# due.net
KiCad netlist of a schematic drawn in EAGLE
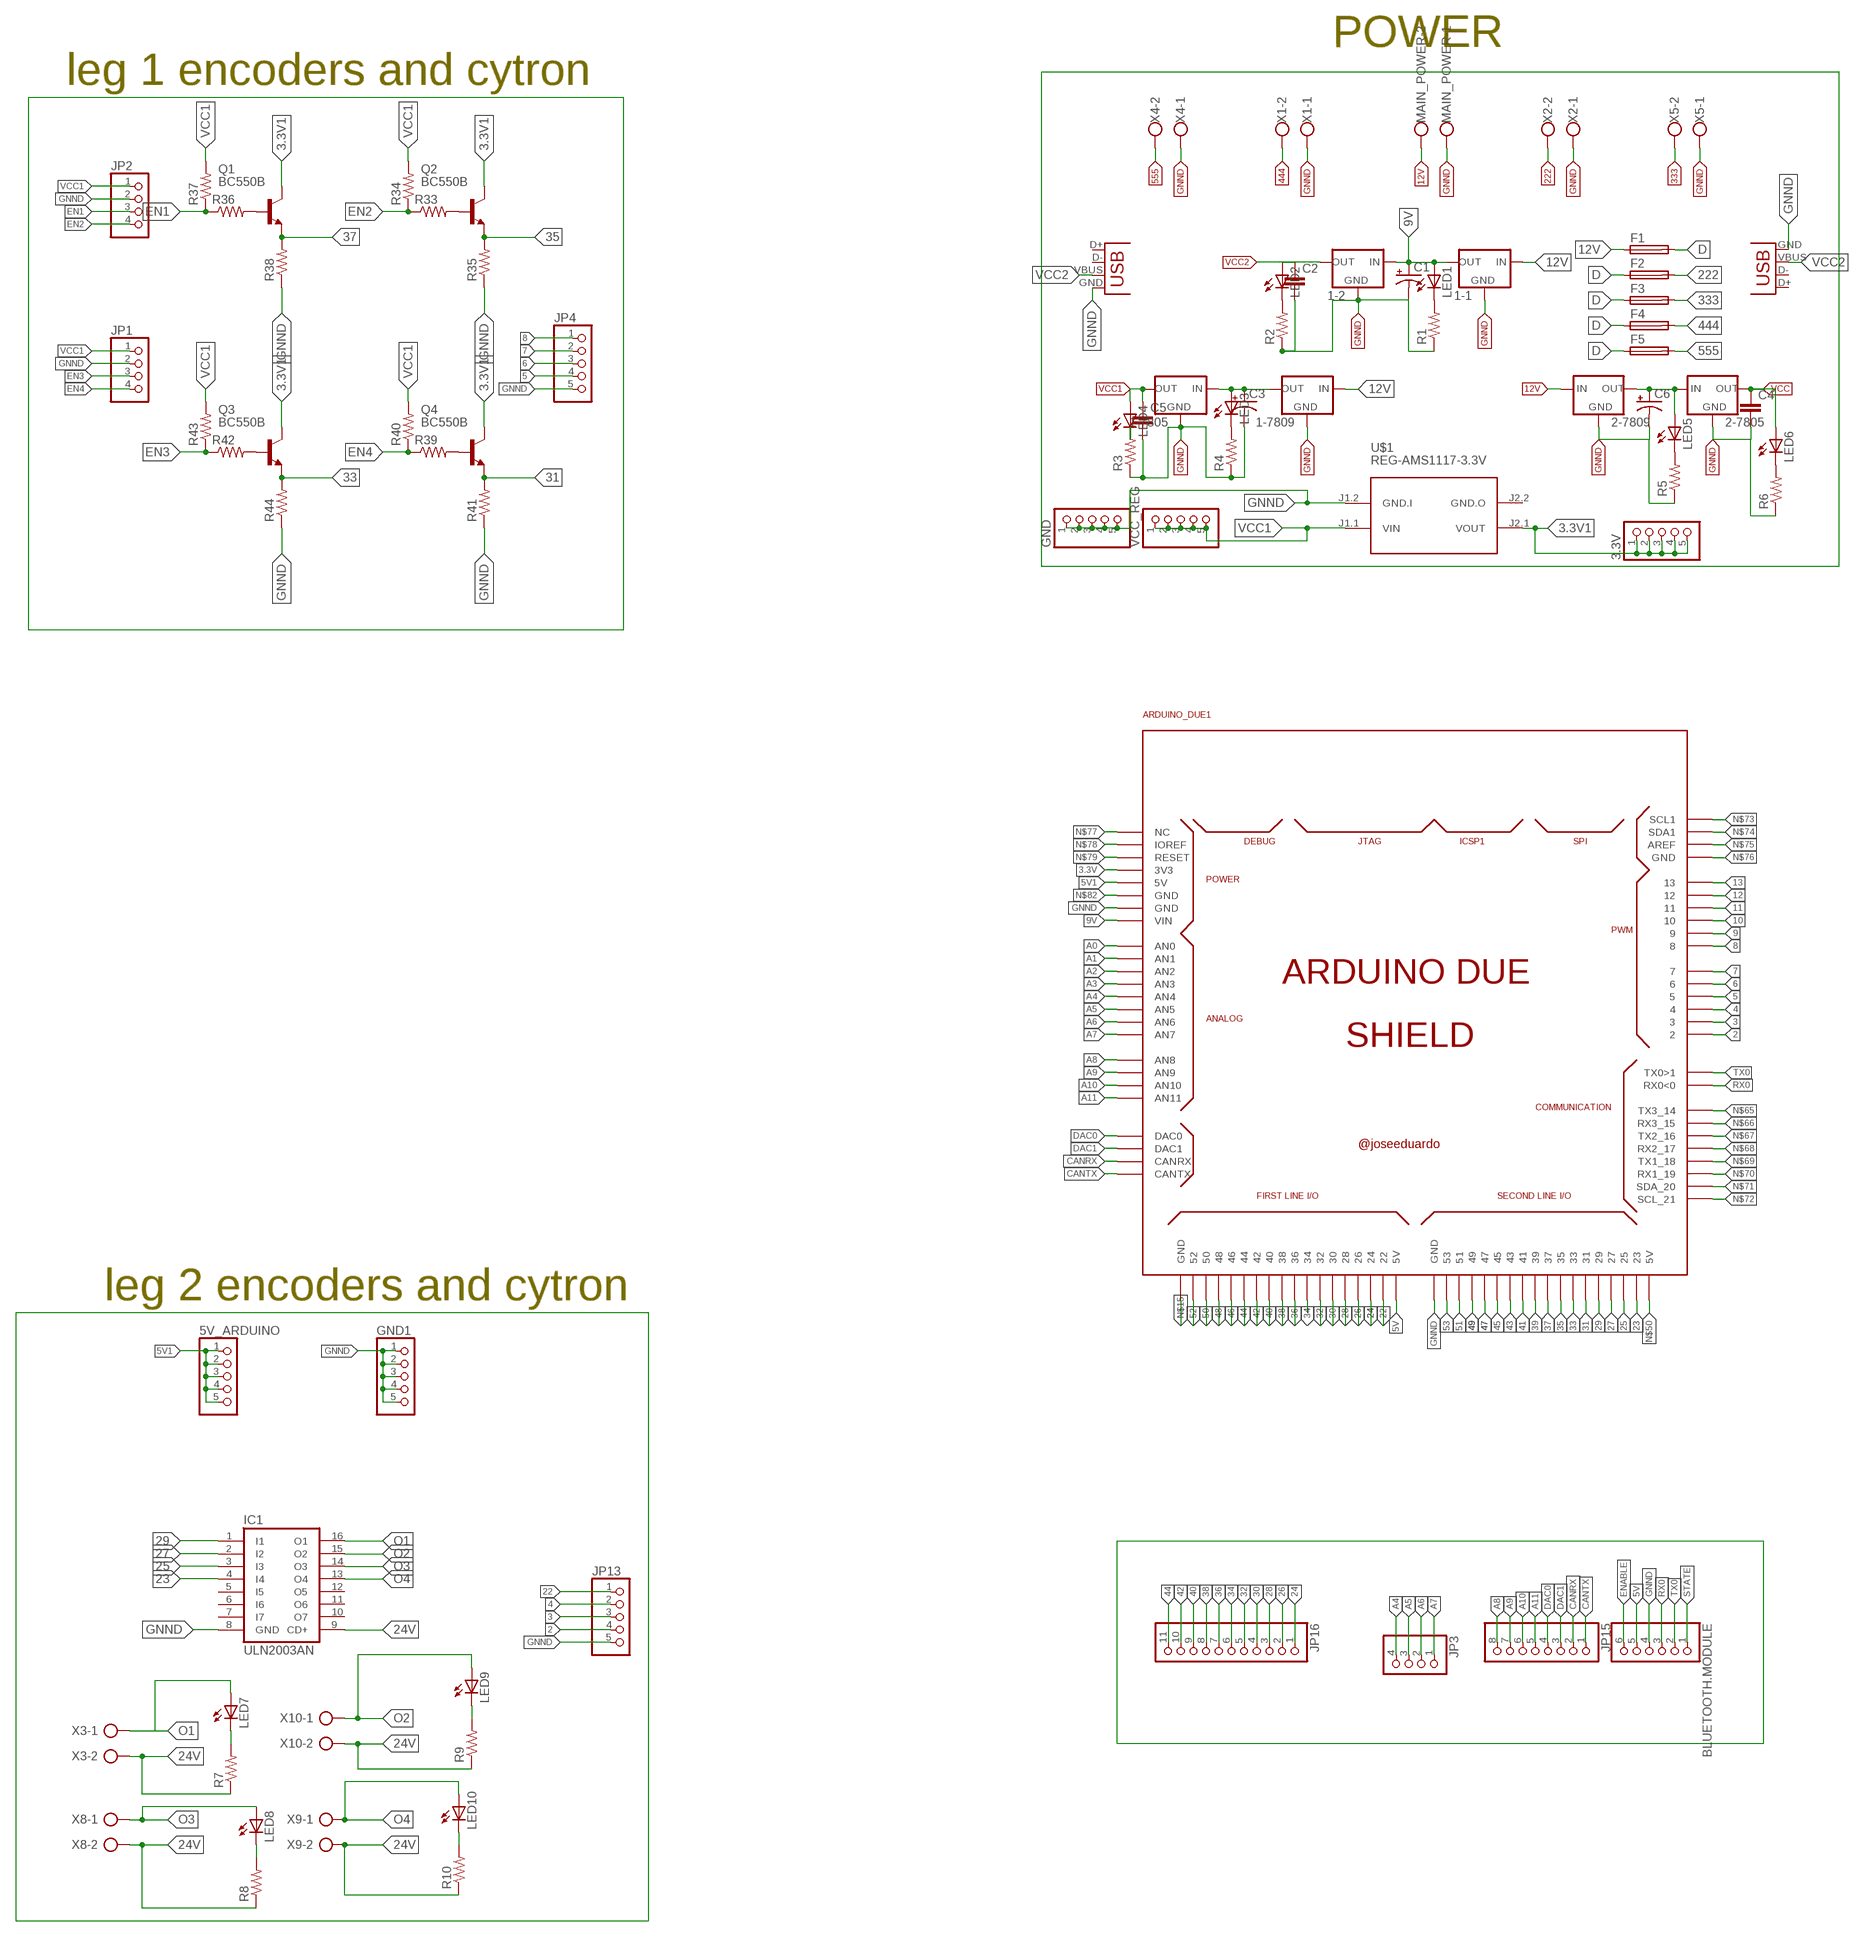
[diagram p0: schematic, sheet 1, part 1 of 2]
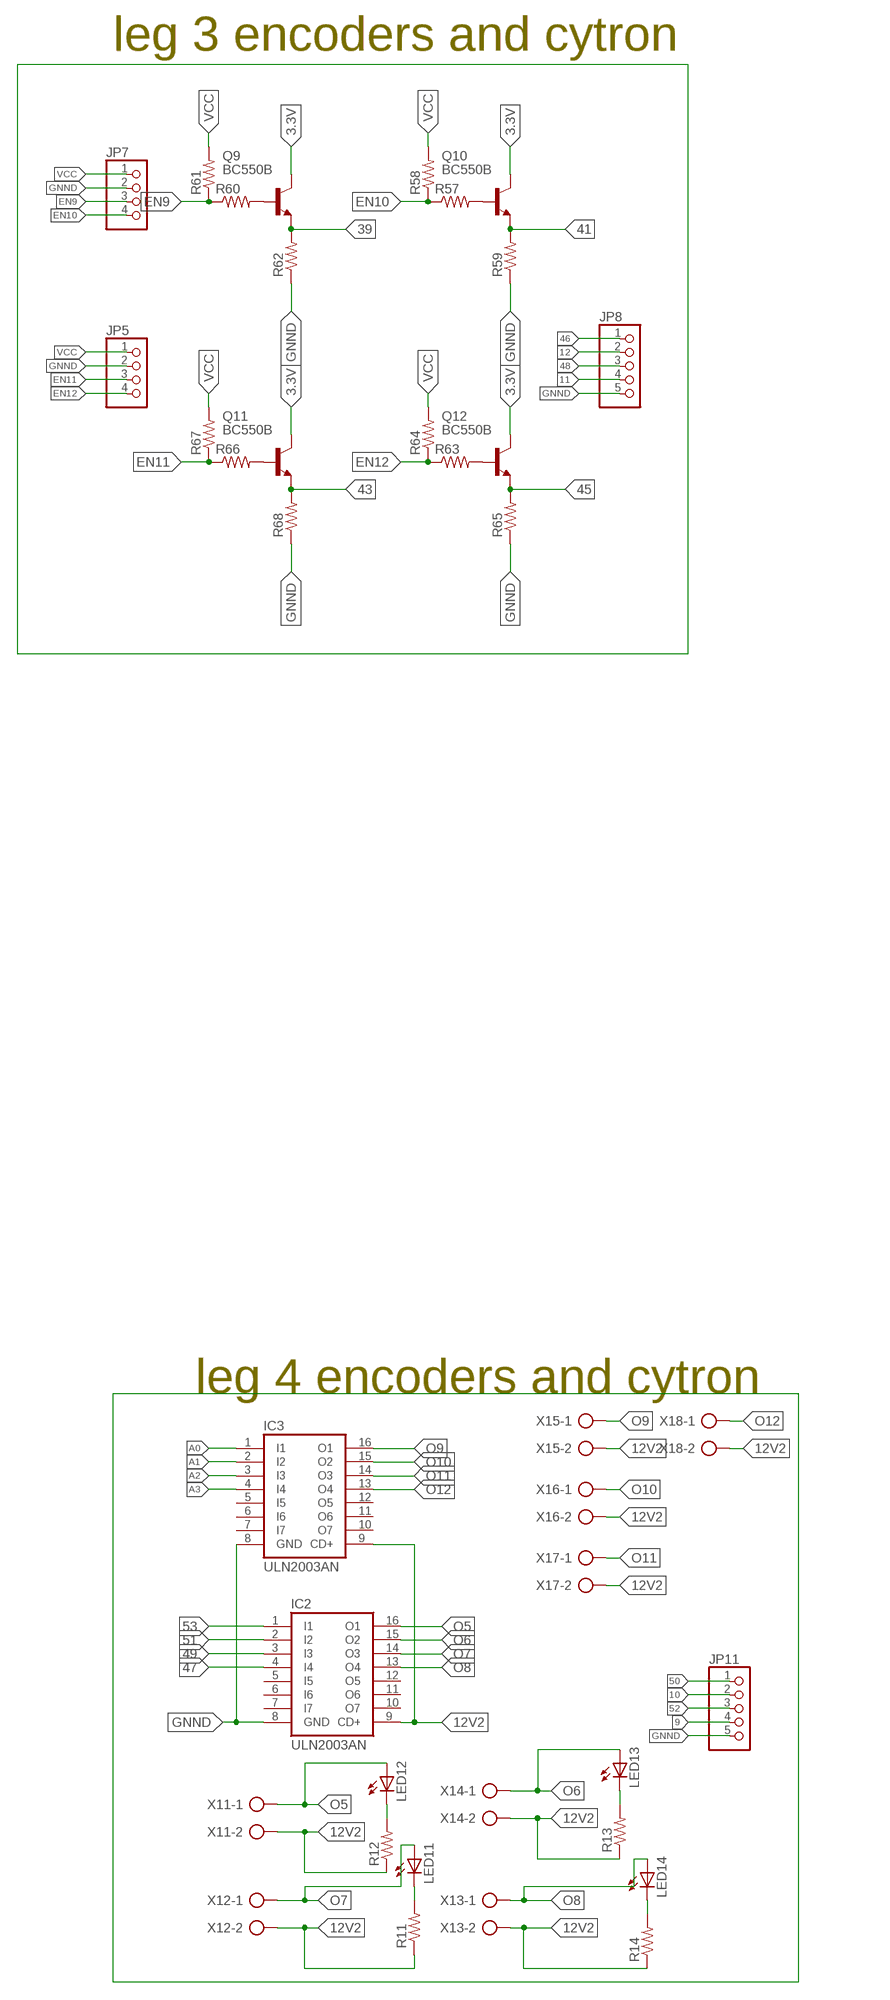
[diagram p1: schematic, sheet 1, part 2 of 2]

(export (version "E")
  (design (tool "Eeschema 10.0.6"))
  (components
    (comp (ref "1-1")
      (value "78XXS")
      (footprint "eagle-import:78XXS")
      (libsource (lib "eagle-import") (part "78XXS"))
    )
    (comp (ref "1-2")
      (value "78XXS")
      (footprint "eagle-import:78XXS")
      (libsource (lib "eagle-import") (part "78XXS"))
    )
    (comp (ref "1-7805")
      (value "78XXS")
      (footprint "eagle-import:78XXS")
      (libsource (lib "eagle-import") (part "78XXS"))
    )
    (comp (ref "1-7809")
      (value "78XXS")
      (footprint "eagle-import:78XXS")
      (libsource (lib "eagle-import") (part "78XXS"))
    )
    (comp (ref "2-7805")
      (value "78XXS")
      (footprint "eagle-import:78XXS")
      (libsource (lib "eagle-import") (part "78XXS"))
    )
    (comp (ref "2-7809")
      (value "78XXS")
      (footprint "eagle-import:78XXS")
      (libsource (lib "eagle-import") (part "78XXS"))
    )
    (comp (ref "3.3V")
      (value "PINHD-1X5")
      (footprint "eagle-import:1X05")
      (libsource (lib "eagle-import") (part "PINHD-1X5"))
    )
    (comp (ref "5V_ARDUINO")
      (value "PINHD-1X5")
      (footprint "eagle-import:1X05")
      (libsource (lib "eagle-import") (part "PINHD-1X5"))
    )
    (comp (ref "ARDUINO_DUE1")
      (value "ARDUINO_DUE_SHIELD")
      (footprint "eagle-import:ARDUINO_DUE_SHIELD")
      (libsource (lib "eagle-import") (part "ARDUINO_DUE_SHIELD"))
    )
    (comp (ref "BLUETOOTH.MODULE")
      (value "PINHD-1X6")
      (footprint "eagle-import:1X06")
      (libsource (lib "eagle-import") (part "PINHD-1X6"))
    )
    (comp (ref "C1")
      (value "CPOL-USE2.5-7")
      (footprint "eagle-import:E2,5-7")
      (libsource (lib "eagle-import") (part "CPOL-USE2.5-7"))
    )
    (comp (ref "C2")
      (value "C-EU025-025X050")
      (footprint "eagle-import:C025-025X050")
      (libsource (lib "eagle-import") (part "C-EU025-025X050"))
    )
    (comp (ref "C3")
      (value "CPOL-USE2.5-7")
      (footprint "eagle-import:E2,5-7")
      (libsource (lib "eagle-import") (part "CPOL-USE2.5-7"))
    )
    (comp (ref "C4")
      (value "C-EU025-025X050")
      (footprint "eagle-import:C025-025X050")
      (libsource (lib "eagle-import") (part "C-EU025-025X050"))
    )
    (comp (ref "C5")
      (value "C-EU025-025X050")
      (footprint "eagle-import:C025-025X050")
      (libsource (lib "eagle-import") (part "C-EU025-025X050"))
    )
    (comp (ref "C6")
      (value "CPOL-USE2.5-7")
      (footprint "eagle-import:E2,5-7")
      (libsource (lib "eagle-import") (part "CPOL-USE2.5-7"))
    )
    (comp (ref "F1")
      (value "SH22,5A")
      (footprint "eagle-import:SH22,5A")
      (fields (field (name "MPN") "0031.7701.11"))
      (libsource (lib "eagle-import") (part "SH22,5A"))
    )
    (comp (ref "F2")
      (value "SH22,5A")
      (footprint "eagle-import:SH22,5A")
      (fields (field (name "MPN") "0031.7701.11"))
      (libsource (lib "eagle-import") (part "SH22,5A"))
    )
    (comp (ref "F3")
      (value "SH22,5A")
      (footprint "eagle-import:SH22,5A")
      (fields (field (name "MPN") "0031.7701.11"))
      (libsource (lib "eagle-import") (part "SH22,5A"))
    )
    (comp (ref "F4")
      (value "SH22,5A")
      (footprint "eagle-import:SH22,5A")
      (fields (field (name "MPN") "0031.7701.11"))
      (libsource (lib "eagle-import") (part "SH22,5A"))
    )
    (comp (ref "F5")
      (value "SH22,5A")
      (footprint "eagle-import:SH22,5A")
      (fields (field (name "MPN") "0031.7701.11"))
      (libsource (lib "eagle-import") (part "SH22,5A"))
    )
    (comp (ref "GND")
      (value "PINHD-1X5")
      (footprint "eagle-import:1X05")
      (libsource (lib "eagle-import") (part "PINHD-1X5"))
    )
    (comp (ref "GND1")
      (value "PINHD-1X5")
      (footprint "eagle-import:1X05")
      (libsource (lib "eagle-import") (part "PINHD-1X5"))
    )
    (comp (ref "IC1")
      (value "ULN2003AN")
      (footprint "eagle-import:DIL16")
      (libsource (lib "eagle-import") (part "ULN2003AN"))
    )
    (comp (ref "IC2")
      (value "ULN2003AN")
      (footprint "eagle-import:DIL16")
      (libsource (lib "eagle-import") (part "ULN2003AN"))
    )
    (comp (ref "IC3")
      (value "ULN2003AN")
      (footprint "eagle-import:DIL16")
      (libsource (lib "eagle-import") (part "ULN2003AN"))
    )
    (comp (ref "JP1")
      (value "PINHD-1X4")
      (footprint "eagle-import:1X04")
      (libsource (lib "eagle-import") (part "PINHD-1X4"))
    )
    (comp (ref "JP2")
      (value "PINHD-1X4")
      (footprint "eagle-import:1X04")
      (libsource (lib "eagle-import") (part "PINHD-1X4"))
    )
    (comp (ref "JP3")
      (value "PINHD-1X4")
      (footprint "eagle-import:1X04")
      (libsource (lib "eagle-import") (part "PINHD-1X4"))
    )
    (comp (ref "JP4")
      (value "PINHD-1X5")
      (footprint "eagle-import:1X05")
      (libsource (lib "eagle-import") (part "PINHD-1X5"))
    )
    (comp (ref "JP5")
      (value "PINHD-1X4")
      (footprint "eagle-import:1X04")
      (libsource (lib "eagle-import") (part "PINHD-1X4"))
    )
    (comp (ref "JP7")
      (value "PINHD-1X4")
      (footprint "eagle-import:1X04")
      (libsource (lib "eagle-import") (part "PINHD-1X4"))
    )
    (comp (ref "JP8")
      (value "PINHD-1X5")
      (footprint "eagle-import:1X05")
      (libsource (lib "eagle-import") (part "PINHD-1X5"))
    )
    (comp (ref "JP11")
      (value "PINHD-1X5")
      (footprint "eagle-import:1X05")
      (libsource (lib "eagle-import") (part "PINHD-1X5"))
    )
    (comp (ref "JP13")
      (value "PINHD-1X5")
      (footprint "eagle-import:1X05")
      (libsource (lib "eagle-import") (part "PINHD-1X5"))
    )
    (comp (ref "JP15")
      (value "PINHD-1X8")
      (footprint "eagle-import:1X08")
      (libsource (lib "eagle-import") (part "PINHD-1X8"))
    )
    (comp (ref "JP16")
      (value "PINHD-1X11")
      (footprint "eagle-import:1X11")
      (libsource (lib "eagle-import") (part "PINHD-1X11"))
    )
    (comp (ref "LED1")
      (value "LED3MM")
      (footprint "eagle-import:LED3MM")
      (libsource (lib "eagle-import") (part "LED3MM"))
    )
    (comp (ref "LED2")
      (value "LED3MM")
      (footprint "eagle-import:LED3MM")
      (libsource (lib "eagle-import") (part "LED3MM"))
    )
    (comp (ref "LED3")
      (value "LED3MM")
      (footprint "eagle-import:LED3MM")
      (libsource (lib "eagle-import") (part "LED3MM"))
    )
    (comp (ref "LED4")
      (value "LED3MM")
      (footprint "eagle-import:LED3MM")
      (libsource (lib "eagle-import") (part "LED3MM"))
    )
    (comp (ref "LED5")
      (value "LED3MM")
      (footprint "eagle-import:LED3MM")
      (libsource (lib "eagle-import") (part "LED3MM"))
    )
    (comp (ref "LED6")
      (value "LED3MM")
      (footprint "eagle-import:LED3MM")
      (libsource (lib "eagle-import") (part "LED3MM"))
    )
    (comp (ref "LED7")
      (value "LED3MM")
      (footprint "eagle-import:LED3MM")
      (libsource (lib "eagle-import") (part "LED3MM"))
    )
    (comp (ref "LED8")
      (value "LED3MM")
      (footprint "eagle-import:LED3MM")
      (libsource (lib "eagle-import") (part "LED3MM"))
    )
    (comp (ref "LED9")
      (value "LED3MM")
      (footprint "eagle-import:LED3MM")
      (libsource (lib "eagle-import") (part "LED3MM"))
    )
    (comp (ref "LED10")
      (value "LED3MM")
      (footprint "eagle-import:LED3MM")
      (libsource (lib "eagle-import") (part "LED3MM"))
    )
    (comp (ref "LED11")
      (value "LED3MM")
      (footprint "eagle-import:LED3MM")
      (libsource (lib "eagle-import") (part "LED3MM"))
    )
    (comp (ref "LED12")
      (value "LED3MM")
      (footprint "eagle-import:LED3MM")
      (libsource (lib "eagle-import") (part "LED3MM"))
    )
    (comp (ref "LED13")
      (value "LED3MM")
      (footprint "eagle-import:LED3MM")
      (libsource (lib "eagle-import") (part "LED3MM"))
    )
    (comp (ref "LED14")
      (value "LED3MM")
      (footprint "eagle-import:LED3MM")
      (libsource (lib "eagle-import") (part "LED3MM"))
    )
    (comp (ref "MAIN_POWER")
      (value "W237-113")
      (footprint "eagle-import:W237-113")
      (libsource (lib "eagle-import") (part "W237-113"))
    )
    (comp (ref "Q1")
      (value "BC550B")
      (footprint "eagle-import:TO92-EBC")
      (libsource (lib "eagle-import") (part "BC550B"))
    )
    (comp (ref "Q2")
      (value "BC550B")
      (footprint "eagle-import:TO92-EBC")
      (libsource (lib "eagle-import") (part "BC550B"))
    )
    (comp (ref "Q3")
      (value "BC550B")
      (footprint "eagle-import:TO92-EBC")
      (libsource (lib "eagle-import") (part "BC550B"))
    )
    (comp (ref "Q4")
      (value "BC550B")
      (footprint "eagle-import:TO92-EBC")
      (libsource (lib "eagle-import") (part "BC550B"))
    )
    (comp (ref "Q9")
      (value "BC550B")
      (footprint "eagle-import:TO92-EBC")
      (libsource (lib "eagle-import") (part "BC550B"))
    )
    (comp (ref "Q10")
      (value "BC550B")
      (footprint "eagle-import:TO92-EBC")
      (libsource (lib "eagle-import") (part "BC550B"))
    )
    (comp (ref "Q11")
      (value "BC550B")
      (footprint "eagle-import:TO92-EBC")
      (libsource (lib "eagle-import") (part "BC550B"))
    )
    (comp (ref "Q12")
      (value "BC550B")
      (footprint "eagle-import:TO92-EBC")
      (libsource (lib "eagle-import") (part "BC550B"))
    )
    (comp (ref "R1")
      (value "R-US_0204/7")
      (footprint "eagle-import:0204_7")
      (libsource (lib "eagle-import") (part "R-US_0204/7"))
    )
    (comp (ref "R2")
      (value "R-US_0204/5")
      (footprint "eagle-import:0204_5")
      (libsource (lib "eagle-import") (part "R-US_0204/5"))
    )
    (comp (ref "R3")
      (value "R-US_0204/5")
      (footprint "eagle-import:0204_5")
      (libsource (lib "eagle-import") (part "R-US_0204/5"))
    )
    (comp (ref "R4")
      (value "R-US_0204/5")
      (footprint "eagle-import:0204_5")
      (libsource (lib "eagle-import") (part "R-US_0204/5"))
    )
    (comp (ref "R5")
      (value "R-US_0204/7")
      (footprint "eagle-import:0204_7")
      (libsource (lib "eagle-import") (part "R-US_0204/7"))
    )
    (comp (ref "R6")
      (value "R-US_0204/5")
      (footprint "eagle-import:0204_5")
      (libsource (lib "eagle-import") (part "R-US_0204/5"))
    )
    (comp (ref "R7")
      (value "R-US_0204/5")
      (footprint "eagle-import:0204_5")
      (libsource (lib "eagle-import") (part "R-US_0204/5"))
    )
    (comp (ref "R8")
      (value "R-US_0204/5")
      (footprint "eagle-import:0204_5")
      (libsource (lib "eagle-import") (part "R-US_0204/5"))
    )
    (comp (ref "R9")
      (value "R-US_0204/5")
      (footprint "eagle-import:0204_5")
      (libsource (lib "eagle-import") (part "R-US_0204/5"))
    )
    (comp (ref "R10")
      (value "R-US_0204/5")
      (footprint "eagle-import:0204_5")
      (libsource (lib "eagle-import") (part "R-US_0204/5"))
    )
    (comp (ref "R11")
      (value "R-US_0204/5")
      (footprint "eagle-import:0204_5")
      (libsource (lib "eagle-import") (part "R-US_0204/5"))
    )
    (comp (ref "R12")
      (value "R-US_0204/5")
      (footprint "eagle-import:0204_5")
      (libsource (lib "eagle-import") (part "R-US_0204/5"))
    )
    (comp (ref "R13")
      (value "R-US_0204/5")
      (footprint "eagle-import:0204_5")
      (libsource (lib "eagle-import") (part "R-US_0204/5"))
    )
    (comp (ref "R14")
      (value "R-US_0204/5")
      (footprint "eagle-import:0204_5")
      (libsource (lib "eagle-import") (part "R-US_0204/5"))
    )
    (comp (ref "R33")
      (value "R-US_0207/12")
      (footprint "eagle-import:0207_12")
      (libsource (lib "eagle-import") (part "R-US_0207/12"))
    )
    (comp (ref "R34")
      (value "R-US_0204/5")
      (footprint "eagle-import:0204_5")
      (libsource (lib "eagle-import") (part "R-US_0204/5"))
    )
    (comp (ref "R35")
      (value "R-US_0207/12")
      (footprint "eagle-import:0207_12")
      (libsource (lib "eagle-import") (part "R-US_0207/12"))
    )
    (comp (ref "R36")
      (value "R-US_0204/7")
      (footprint "eagle-import:0204_7")
      (libsource (lib "eagle-import") (part "R-US_0204/7"))
    )
    (comp (ref "R37")
      (value "R-US_0204/5")
      (footprint "eagle-import:0204_5")
      (libsource (lib "eagle-import") (part "R-US_0204/5"))
    )
    (comp (ref "R38")
      (value "R-US_0204/7")
      (footprint "eagle-import:0204_7")
      (libsource (lib "eagle-import") (part "R-US_0204/7"))
    )
    (comp (ref "R39")
      (value "R-US_0207/12")
      (footprint "eagle-import:0207_12")
      (libsource (lib "eagle-import") (part "R-US_0207/12"))
    )
    (comp (ref "R40")
      (value "R-US_0204/5")
      (footprint "eagle-import:0204_5")
      (libsource (lib "eagle-import") (part "R-US_0204/5"))
    )
    (comp (ref "R41")
      (value "R-US_0207/12")
      (footprint "eagle-import:0207_12")
      (libsource (lib "eagle-import") (part "R-US_0207/12"))
    )
    (comp (ref "R42")
      (value "R-US_0204/7")
      (footprint "eagle-import:0204_7")
      (libsource (lib "eagle-import") (part "R-US_0204/7"))
    )
    (comp (ref "R43")
      (value "R-US_0204/5")
      (footprint "eagle-import:0204_5")
      (libsource (lib "eagle-import") (part "R-US_0204/5"))
    )
    (comp (ref "R44")
      (value "R-US_0204/7")
      (footprint "eagle-import:0204_7")
      (libsource (lib "eagle-import") (part "R-US_0204/7"))
    )
    (comp (ref "R57")
      (value "R-US_0207/12")
      (footprint "eagle-import:0207_12")
      (libsource (lib "eagle-import") (part "R-US_0207/12"))
    )
    (comp (ref "R58")
      (value "R-US_0204/5")
      (footprint "eagle-import:0204_5")
      (libsource (lib "eagle-import") (part "R-US_0204/5"))
    )
    (comp (ref "R59")
      (value "R-US_0207/12")
      (footprint "eagle-import:0207_12")
      (libsource (lib "eagle-import") (part "R-US_0207/12"))
    )
    (comp (ref "R60")
      (value "R-US_0204/7")
      (footprint "eagle-import:0204_7")
      (libsource (lib "eagle-import") (part "R-US_0204/7"))
    )
    (comp (ref "R61")
      (value "R-US_0204/5")
      (footprint "eagle-import:0204_5")
      (libsource (lib "eagle-import") (part "R-US_0204/5"))
    )
    (comp (ref "R62")
      (value "R-US_0204/7")
      (footprint "eagle-import:0204_7")
      (libsource (lib "eagle-import") (part "R-US_0204/7"))
    )
    (comp (ref "R63")
      (value "R-US_0207/12")
      (footprint "eagle-import:0207_12")
      (libsource (lib "eagle-import") (part "R-US_0207/12"))
    )
    (comp (ref "R64")
      (value "R-US_0204/5")
      (footprint "eagle-import:0204_5")
      (libsource (lib "eagle-import") (part "R-US_0204/5"))
    )
    (comp (ref "R65")
      (value "R-US_0207/12")
      (footprint "eagle-import:0207_12")
      (libsource (lib "eagle-import") (part "R-US_0207/12"))
    )
    (comp (ref "R66")
      (value "R-US_0204/7")
      (footprint "eagle-import:0204_7")
      (libsource (lib "eagle-import") (part "R-US_0204/7"))
    )
    (comp (ref "R67")
      (value "R-US_0204/5")
      (footprint "eagle-import:0204_5")
      (libsource (lib "eagle-import") (part "R-US_0204/5"))
    )
    (comp (ref "R68")
      (value "R-US_0204/7")
      (footprint "eagle-import:0204_7")
      (libsource (lib "eagle-import") (part "R-US_0204/7"))
    )
    (comp (ref "U$1")
      (value "REG-AMS1117-3.3V")
      (footprint "eagle-import:REG-AMS1117")
      (libsource (lib "eagle-import") (part "REG-AMS1117-3.3V"))
    )
    (comp (ref "VCC_REG")
      (value "PINHD-1X5")
      (footprint "eagle-import:1X05")
      (libsource (lib "eagle-import") (part "PINHD-1X5"))
    )
    (comp (ref "X1")
      (value "W237-113")
      (footprint "eagle-import:W237-113")
      (libsource (lib "eagle-import") (part "W237-113"))
    )
    (comp (ref "X2")
      (value "W237-113")
      (footprint "eagle-import:W237-113")
      (libsource (lib "eagle-import") (part "W237-113"))
    )
    (comp (ref "X3")
      (value "AK300/2")
      (footprint "eagle-import:AK300_2")
      (libsource (lib "eagle-import") (part "AK300/2"))
    )
    (comp (ref "X4")
      (value "W237-113")
      (footprint "eagle-import:W237-113")
      (libsource (lib "eagle-import") (part "W237-113"))
    )
    (comp (ref "X5")
      (value "W237-113")
      (footprint "eagle-import:W237-113")
      (libsource (lib "eagle-import") (part "W237-113"))
    )
    (comp (ref "X6")
      (value "USB-A-H")
      (footprint "eagle-import:USB-A-H")
      (libsource (lib "eagle-import") (part "USB-A-H"))
    )
    (comp (ref "X7")
      (value "USB-A-H")
      (footprint "eagle-import:USB-A-H")
      (libsource (lib "eagle-import") (part "USB-A-H"))
    )
    (comp (ref "X8")
      (value "AK300/2")
      (footprint "eagle-import:AK300_2")
      (libsource (lib "eagle-import") (part "AK300/2"))
    )
    (comp (ref "X9")
      (value "AK300/2")
      (footprint "eagle-import:AK300_2")
      (libsource (lib "eagle-import") (part "AK300/2"))
    )
    (comp (ref "X10")
      (value "AK300/2")
      (footprint "eagle-import:AK300_2")
      (libsource (lib "eagle-import") (part "AK300/2"))
    )
    (comp (ref "X11")
      (value "AK300/2")
      (footprint "eagle-import:AK300_2")
      (libsource (lib "eagle-import") (part "AK300/2"))
    )
    (comp (ref "X12")
      (value "AK300/2")
      (footprint "eagle-import:AK300_2")
      (libsource (lib "eagle-import") (part "AK300/2"))
    )
    (comp (ref "X13")
      (value "AK300/2")
      (footprint "eagle-import:AK300_2")
      (libsource (lib "eagle-import") (part "AK300/2"))
    )
    (comp (ref "X14")
      (value "AK300/2")
      (footprint "eagle-import:AK300_2")
      (libsource (lib "eagle-import") (part "AK300/2"))
    )
    (comp (ref "X15")
      (value "AK300/2")
      (footprint "eagle-import:AK300_2")
      (libsource (lib "eagle-import") (part "AK300/2"))
    )
    (comp (ref "X16")
      (value "AK300/2")
      (footprint "eagle-import:AK300_2")
      (libsource (lib "eagle-import") (part "AK300/2"))
    )
    (comp (ref "X17")
      (value "AK300/2")
      (footprint "eagle-import:AK300_2")
      (libsource (lib "eagle-import") (part "AK300/2"))
    )
    (comp (ref "X18")
      (value "AK300/2")
      (footprint "eagle-import:AK300_2")
      (libsource (lib "eagle-import") (part "AK300/2"))
    )
  )
  (nets
    (net (code "1") (name "2") (class "Default")
      (node (ref "ARDUINO_DUE1") (pin "2") (pinfunction "2_2") (pintype "bidirectional"))
      (node (ref "JP13") (pin "4") (pinfunction "4_4") (pintype "passive"))
    )
    (net (code "2") (name "3") (class "Default")
      (node (ref "ARDUINO_DUE1") (pin "3") (pinfunction "3_3") (pintype "bidirectional"))
      (node (ref "JP13") (pin "3") (pinfunction "3_3") (pintype "passive"))
    )
    (net (code "3") (name "3.3V") (class "Default")
      (node (ref "ARDUINO_DUE1") (pin "3V3") (pinfunction "3V3_3V3") (pintype "bidirectional"))
      (node (ref "Q10") (pin "C") (pinfunction "C_C") (pintype "passive"))
      (node (ref "Q11") (pin "C") (pinfunction "C_C") (pintype "passive"))
      (node (ref "Q12") (pin "C") (pinfunction "C_C") (pintype "passive"))
      (node (ref "Q9") (pin "C") (pinfunction "C_C") (pintype "passive"))
    )
    (net (code "4") (name "3.3V1") (class "Default")
      (node (ref "3.3V") (pin "1") (pinfunction "1_1") (pintype "passive"))
      (node (ref "3.3V") (pin "2") (pinfunction "2_2") (pintype "passive"))
      (node (ref "3.3V") (pin "3") (pinfunction "3_3") (pintype "passive"))
      (node (ref "3.3V") (pin "4") (pinfunction "4_4") (pintype "passive"))
      (node (ref "3.3V") (pin "5") (pinfunction "5_5") (pintype "passive"))
      (node (ref "Q1") (pin "C") (pinfunction "C_C") (pintype "passive"))
      (node (ref "Q2") (pin "C") (pinfunction "C_C") (pintype "passive"))
      (node (ref "Q3") (pin "C") (pinfunction "C_C") (pintype "passive"))
      (node (ref "Q4") (pin "C") (pinfunction "C_C") (pintype "passive"))
      (node (ref "U$1") (pin "J2.1") (pinfunction "VOUT_J2.1") (pintype "bidirectional"))
    )
    (net (code "5") (name "4") (class "Default")
      (node (ref "ARDUINO_DUE1") (pin "4") (pinfunction "4_4") (pintype "bidirectional"))
      (node (ref "JP13") (pin "2") (pinfunction "2_2") (pintype "passive"))
    )
    (net (code "6") (name "5") (class "Default")
      (node (ref "ARDUINO_DUE1") (pin "5") (pinfunction "5_5") (pintype "bidirectional"))
      (node (ref "JP4") (pin "4") (pinfunction "4_4") (pintype "passive"))
    )
    (net (code "7") (name "5V") (class "Default")
      (node (ref "ARDUINO_DUE1") (pin "5V0_1") (pinfunction "5V_5V0_1") (pintype "bidirectional"))
      (node (ref "BLUETOOTH.MODULE") (pin "5") (pinfunction "5_5") (pintype "passive"))
    )
    (net (code "8") (name "5V1") (class "Default")
      (node (ref "5V_ARDUINO") (pin "1") (pinfunction "1_1") (pintype "passive"))
      (node (ref "5V_ARDUINO") (pin "2") (pinfunction "2_2") (pintype "passive"))
      (node (ref "5V_ARDUINO") (pin "3") (pinfunction "3_3") (pintype "passive"))
      (node (ref "5V_ARDUINO") (pin "4") (pinfunction "4_4") (pintype "passive"))
      (node (ref "5V_ARDUINO") (pin "5") (pinfunction "5_5") (pintype "passive"))
      (node (ref "ARDUINO_DUE1") (pin "5V0") (pinfunction "5V_5V0") (pintype "bidirectional"))
    )
    (net (code "9") (name "6") (class "Default")
      (node (ref "ARDUINO_DUE1") (pin "6") (pinfunction "6_6") (pintype "bidirectional"))
      (node (ref "JP4") (pin "3") (pinfunction "3_3") (pintype "passive"))
    )
    (net (code "10") (name "7") (class "Default")
      (node (ref "ARDUINO_DUE1") (pin "7") (pinfunction "7_7") (pintype "bidirectional"))
      (node (ref "JP4") (pin "2") (pinfunction "2_2") (pintype "passive"))
    )
    (net (code "11") (name "8") (class "Default")
      (node (ref "ARDUINO_DUE1") (pin "8") (pinfunction "8_8") (pintype "bidirectional"))
      (node (ref "JP4") (pin "1") (pinfunction "1_1") (pintype "passive"))
    )
    (net (code "12") (name "9") (class "Default")
      (node (ref "ARDUINO_DUE1") (pin "9") (pinfunction "9_9") (pintype "bidirectional"))
      (node (ref "JP11") (pin "4") (pinfunction "4_4") (pintype "passive"))
    )
    (net (code "13") (name "9V") (class "Default")
      (node (ref "1-1") (pin "OUT") (pinfunction "OUT_OUT") (pintype "passive"))
      (node (ref "1-2") (pin "IN") (pinfunction "IN_IN") (pintype "input"))
      (node (ref "ARDUINO_DUE1") (pin "VIN") (pinfunction "VIN_VIN") (pintype "bidirectional"))
      (node (ref "C1") (pin "+") (pinfunction "+_+") (pintype "passive"))
      (node (ref "LED1") (pin "A") (pinfunction "A_A") (pintype "passive"))
    )
    (net (code "14") (name "10") (class "Default")
      (node (ref "ARDUINO_DUE1") (pin "10") (pinfunction "10_10") (pintype "bidirectional"))
      (node (ref "JP11") (pin "2") (pinfunction "2_2") (pintype "passive"))
    )
    (net (code "15") (name "11") (class "Default")
      (node (ref "ARDUINO_DUE1") (pin "11") (pinfunction "11_11") (pintype "bidirectional"))
      (node (ref "JP8") (pin "4") (pinfunction "4_4") (pintype "passive"))
    )
    (net (code "16") (name "12") (class "Default")
      (node (ref "ARDUINO_DUE1") (pin "12") (pinfunction "12_12") (pintype "bidirectional"))
      (node (ref "JP8") (pin "2") (pinfunction "2_2") (pintype "passive"))
    )
    (net (code "17") (name "12V") (class "Default")
      (node (ref "1-1") (pin "IN") (pinfunction "IN_IN") (pintype "input"))
      (node (ref "1-7809") (pin "IN") (pinfunction "IN_IN") (pintype "input"))
      (node (ref "2-7809") (pin "IN") (pinfunction "IN_IN") (pintype "input"))
      (node (ref "F1") (pin "1") (pinfunction "1_1") (pintype "passive"))
      (node (ref "MAIN_POWER") (pin "2") (pinfunction "KL_2") (pintype "passive"))
    )
    (net (code "18") (name "12V2") (class "Default")
      (node (ref "IC2") (pin "9") (pinfunction "CD+_9") (pintype "passive"))
      (node (ref "IC3") (pin "9") (pinfunction "CD+_9") (pintype "passive"))
      (node (ref "R11") (pin "1") (pinfunction "1_1") (pintype "passive"))
      (node (ref "R12") (pin "1") (pinfunction "1_1") (pintype "passive"))
      (node (ref "R13") (pin "1") (pinfunction "1_1") (pintype "passive"))
      (node (ref "R14") (pin "1") (pinfunction "1_1") (pintype "passive"))
      (node (ref "X11") (pin "2") (pinfunction "KL_2") (pintype "passive"))
      (node (ref "X12") (pin "2") (pinfunction "KL_2") (pintype "passive"))
      (node (ref "X13") (pin "2") (pinfunction "KL_2") (pintype "passive"))
      (node (ref "X14") (pin "2") (pinfunction "KL_2") (pintype "passive"))
      (node (ref "X15") (pin "2") (pinfunction "KL_2") (pintype "passive"))
      (node (ref "X16") (pin "2") (pinfunction "KL_2") (pintype "passive"))
      (node (ref "X17") (pin "2") (pinfunction "KL_2") (pintype "passive"))
      (node (ref "X18") (pin "2") (pinfunction "KL_2") (pintype "passive"))
    )
    (net (code "19") (name "13") (class "Default")
      (node (ref "ARDUINO_DUE1") (pin "13") (pinfunction "13_13") (pintype "bidirectional"))
    )
    (net (code "20") (name "22") (class "Default")
      (node (ref "ARDUINO_DUE1") (pin "22") (pinfunction "22_22") (pintype "bidirectional"))
      (node (ref "JP13") (pin "1") (pinfunction "1_1") (pintype "passive"))
    )
    (net (code "21") (name "23") (class "Default")
      (node (ref "ARDUINO_DUE1") (pin "23") (pinfunction "23_23") (pintype "bidirectional"))
      (node (ref "IC1") (pin "4") (pinfunction "I4_4") (pintype "input"))
    )
    (net (code "22") (name "24") (class "Default")
      (node (ref "ARDUINO_DUE1") (pin "24") (pinfunction "24_24") (pintype "bidirectional"))
      (node (ref "JP16") (pin "1") (pinfunction "1_1") (pintype "passive"))
    )
    (net (code "23") (name "24V") (class "Default")
      (node (ref "IC1") (pin "9") (pinfunction "CD+_9") (pintype "passive"))
      (node (ref "R10") (pin "1") (pinfunction "1_1") (pintype "passive"))
      (node (ref "R7") (pin "1") (pinfunction "1_1") (pintype "passive"))
      (node (ref "R8") (pin "1") (pinfunction "1_1") (pintype "passive"))
      (node (ref "R9") (pin "1") (pinfunction "1_1") (pintype "passive"))
      (node (ref "X10") (pin "2") (pinfunction "KL_2") (pintype "passive"))
      (node (ref "X3") (pin "2") (pinfunction "KL_2") (pintype "passive"))
      (node (ref "X8") (pin "2") (pinfunction "KL_2") (pintype "passive"))
      (node (ref "X9") (pin "2") (pinfunction "KL_2") (pintype "passive"))
    )
    (net (code "24") (name "25") (class "Default")
      (node (ref "ARDUINO_DUE1") (pin "25") (pinfunction "25_25") (pintype "bidirectional"))
      (node (ref "IC1") (pin "3") (pinfunction "I3_3") (pintype "input"))
    )
    (net (code "25") (name "26") (class "Default")
      (node (ref "ARDUINO_DUE1") (pin "26") (pinfunction "26_26") (pintype "bidirectional"))
      (node (ref "JP16") (pin "2") (pinfunction "2_2") (pintype "passive"))
    )
    (net (code "26") (name "27") (class "Default")
      (node (ref "ARDUINO_DUE1") (pin "27") (pinfunction "27_27") (pintype "bidirectional"))
      (node (ref "IC1") (pin "2") (pinfunction "I2_2") (pintype "input"))
    )
    (net (code "27") (name "28") (class "Default")
      (node (ref "ARDUINO_DUE1") (pin "28") (pinfunction "28_28") (pintype "bidirectional"))
      (node (ref "JP16") (pin "3") (pinfunction "3_3") (pintype "passive"))
    )
    (net (code "28") (name "29") (class "Default")
      (node (ref "ARDUINO_DUE1") (pin "29") (pinfunction "29_29") (pintype "bidirectional"))
      (node (ref "IC1") (pin "1") (pinfunction "I1_1") (pintype "input"))
    )
    (net (code "29") (name "30") (class "Default")
      (node (ref "ARDUINO_DUE1") (pin "30") (pinfunction "30_30") (pintype "bidirectional"))
      (node (ref "JP16") (pin "4") (pinfunction "4_4") (pintype "passive"))
    )
    (net (code "30") (name "31") (class "Default")
      (node (ref "ARDUINO_DUE1") (pin "31") (pinfunction "31_31") (pintype "bidirectional"))
      (node (ref "Q4") (pin "E") (pinfunction "E_E") (pintype "passive"))
      (node (ref "R41") (pin "2") (pinfunction "2_2") (pintype "passive"))
    )
    (net (code "31") (name "32") (class "Default")
      (node (ref "ARDUINO_DUE1") (pin "32") (pinfunction "32_32") (pintype "bidirectional"))
      (node (ref "JP16") (pin "5") (pinfunction "5_5") (pintype "passive"))
    )
    (net (code "32") (name "33") (class "Default")
      (node (ref "ARDUINO_DUE1") (pin "33") (pinfunction "33_33") (pintype "bidirectional"))
      (node (ref "Q3") (pin "E") (pinfunction "E_E") (pintype "passive"))
      (node (ref "R44") (pin "2") (pinfunction "2_2") (pintype "passive"))
    )
    (net (code "33") (name "34") (class "Default")
      (node (ref "ARDUINO_DUE1") (pin "34") (pinfunction "34_34") (pintype "bidirectional"))
      (node (ref "JP16") (pin "6") (pinfunction "6_6") (pintype "passive"))
    )
    (net (code "34") (name "35") (class "Default")
      (node (ref "ARDUINO_DUE1") (pin "35") (pinfunction "35_35") (pintype "bidirectional"))
      (node (ref "Q2") (pin "E") (pinfunction "E_E") (pintype "passive"))
      (node (ref "R35") (pin "2") (pinfunction "2_2") (pintype "passive"))
    )
    (net (code "35") (name "36") (class "Default")
      (node (ref "ARDUINO_DUE1") (pin "36") (pinfunction "36_36") (pintype "bidirectional"))
      (node (ref "JP16") (pin "7") (pinfunction "7_7") (pintype "passive"))
    )
    (net (code "36") (name "37") (class "Default")
      (node (ref "ARDUINO_DUE1") (pin "37") (pinfunction "37_37") (pintype "bidirectional"))
      (node (ref "Q1") (pin "E") (pinfunction "E_E") (pintype "passive"))
      (node (ref "R38") (pin "2") (pinfunction "2_2") (pintype "passive"))
    )
    (net (code "37") (name "38") (class "Default")
      (node (ref "ARDUINO_DUE1") (pin "38") (pinfunction "38_38") (pintype "bidirectional"))
      (node (ref "JP16") (pin "8") (pinfunction "8_8") (pintype "passive"))
    )
    (net (code "38") (name "39") (class "Default")
      (node (ref "ARDUINO_DUE1") (pin "39") (pinfunction "39_39") (pintype "bidirectional"))
      (node (ref "Q9") (pin "E") (pinfunction "E_E") (pintype "passive"))
      (node (ref "R62") (pin "2") (pinfunction "2_2") (pintype "passive"))
    )
    (net (code "39") (name "40") (class "Default")
      (node (ref "ARDUINO_DUE1") (pin "40") (pinfunction "40_40") (pintype "bidirectional"))
      (node (ref "JP16") (pin "9") (pinfunction "9_9") (pintype "passive"))
    )
    (net (code "40") (name "41") (class "Default")
      (node (ref "ARDUINO_DUE1") (pin "41") (pinfunction "41_41") (pintype "bidirectional"))
      (node (ref "Q10") (pin "E") (pinfunction "E_E") (pintype "passive"))
      (node (ref "R59") (pin "2") (pinfunction "2_2") (pintype "passive"))
    )
    (net (code "41") (name "42") (class "Default")
      (node (ref "ARDUINO_DUE1") (pin "42") (pinfunction "42_42") (pintype "bidirectional"))
      (node (ref "JP16") (pin "10") (pinfunction "10_10") (pintype "passive"))
    )
    (net (code "42") (name "43") (class "Default")
      (node (ref "ARDUINO_DUE1") (pin "43") (pinfunction "43_43") (pintype "bidirectional"))
      (node (ref "Q11") (pin "E") (pinfunction "E_E") (pintype "passive"))
      (node (ref "R68") (pin "2") (pinfunction "2_2") (pintype "passive"))
    )
    (net (code "43") (name "44") (class "Default")
      (node (ref "ARDUINO_DUE1") (pin "44") (pinfunction "44_44") (pintype "bidirectional"))
      (node (ref "JP16") (pin "11") (pinfunction "11_11") (pintype "passive"))
    )
    (net (code "44") (name "45") (class "Default")
      (node (ref "ARDUINO_DUE1") (pin "45") (pinfunction "45_45") (pintype "bidirectional"))
      (node (ref "Q12") (pin "E") (pinfunction "E_E") (pintype "passive"))
      (node (ref "R65") (pin "2") (pinfunction "2_2") (pintype "passive"))
    )
    (net (code "45") (name "46") (class "Default")
      (node (ref "ARDUINO_DUE1") (pin "46") (pinfunction "46_46") (pintype "bidirectional"))
      (node (ref "JP8") (pin "1") (pinfunction "1_1") (pintype "passive"))
    )
    (net (code "46") (name "47") (class "Default")
      (node (ref "ARDUINO_DUE1") (pin "47") (pinfunction "47_47") (pintype "bidirectional"))
      (node (ref "IC2") (pin "4") (pinfunction "I4_4") (pintype "input"))
    )
    (net (code "47") (name "48") (class "Default")
      (node (ref "ARDUINO_DUE1") (pin "48") (pinfunction "48_48") (pintype "bidirectional"))
      (node (ref "JP8") (pin "3") (pinfunction "3_3") (pintype "passive"))
    )
    (net (code "48") (name "49") (class "Default")
      (node (ref "ARDUINO_DUE1") (pin "49") (pinfunction "49_49") (pintype "bidirectional"))
      (node (ref "IC2") (pin "3") (pinfunction "I3_3") (pintype "input"))
    )
    (net (code "49") (name "50") (class "Default")
      (node (ref "ARDUINO_DUE1") (pin "50") (pinfunction "50_50") (pintype "bidirectional"))
      (node (ref "JP11") (pin "1") (pinfunction "1_1") (pintype "passive"))
    )
    (net (code "50") (name "51") (class "Default")
      (node (ref "ARDUINO_DUE1") (pin "51") (pinfunction "51_51") (pintype "bidirectional"))
      (node (ref "IC2") (pin "2") (pinfunction "I2_2") (pintype "input"))
    )
    (net (code "51") (name "52") (class "Default")
      (node (ref "ARDUINO_DUE1") (pin "52") (pinfunction "52_52") (pintype "bidirectional"))
      (node (ref "JP11") (pin "3") (pinfunction "3_3") (pintype "passive"))
    )
    (net (code "52") (name "53") (class "Default")
      (node (ref "ARDUINO_DUE1") (pin "53") (pinfunction "53_53") (pintype "bidirectional"))
      (node (ref "IC2") (pin "1") (pinfunction "I1_1") (pintype "input"))
    )
    (net (code "53") (name "222") (class "Default")
      (node (ref "F2") (pin "2") (pinfunction "2_2") (pintype "passive"))
      (node (ref "X2") (pin "2") (pinfunction "KL_2") (pintype "passive"))
    )
    (net (code "54") (name "333") (class "Default")
      (node (ref "F3") (pin "2") (pinfunction "2_2") (pintype "passive"))
      (node (ref "X5") (pin "2") (pinfunction "KL_2") (pintype "passive"))
    )
    (net (code "55") (name "444") (class "Default")
      (node (ref "F4") (pin "2") (pinfunction "2_2") (pintype "passive"))
      (node (ref "X1") (pin "2") (pinfunction "KL_2") (pintype "passive"))
    )
    (net (code "56") (name "555") (class "Default")
      (node (ref "F5") (pin "2") (pinfunction "2_2") (pintype "passive"))
      (node (ref "X4") (pin "2") (pinfunction "KL_2") (pintype "passive"))
    )
    (net (code "57") (name "A0") (class "Default")
      (node (ref "ARDUINO_DUE1") (pin "A0") (pinfunction "AN0_A0") (pintype "bidirectional"))
      (node (ref "IC3") (pin "1") (pinfunction "I1_1") (pintype "input"))
    )
    (net (code "58") (name "A1") (class "Default")
      (node (ref "ARDUINO_DUE1") (pin "A1") (pinfunction "AN1_A1") (pintype "bidirectional"))
      (node (ref "IC3") (pin "2") (pinfunction "I2_2") (pintype "input"))
    )
    (net (code "59") (name "A2") (class "Default")
      (node (ref "ARDUINO_DUE1") (pin "A2") (pinfunction "AN2_A2") (pintype "bidirectional"))
      (node (ref "IC3") (pin "3") (pinfunction "I3_3") (pintype "input"))
    )
    (net (code "60") (name "A3") (class "Default")
      (node (ref "ARDUINO_DUE1") (pin "A3") (pinfunction "AN3_A3") (pintype "bidirectional"))
      (node (ref "IC3") (pin "4") (pinfunction "I4_4") (pintype "input"))
    )
    (net (code "61") (name "A4") (class "Default")
      (node (ref "ARDUINO_DUE1") (pin "A4") (pinfunction "AN4_A4") (pintype "bidirectional"))
      (node (ref "JP3") (pin "4") (pinfunction "4_4") (pintype "passive"))
    )
    (net (code "62") (name "A5") (class "Default")
      (node (ref "ARDUINO_DUE1") (pin "A5") (pinfunction "AN5_A5") (pintype "bidirectional"))
      (node (ref "JP3") (pin "3") (pinfunction "3_3") (pintype "passive"))
    )
    (net (code "63") (name "A6") (class "Default")
      (node (ref "ARDUINO_DUE1") (pin "A6") (pinfunction "AN6_A6") (pintype "bidirectional"))
      (node (ref "JP3") (pin "2") (pinfunction "2_2") (pintype "passive"))
    )
    (net (code "64") (name "A7") (class "Default")
      (node (ref "ARDUINO_DUE1") (pin "A7") (pinfunction "AN7_A7") (pintype "bidirectional"))
      (node (ref "JP3") (pin "1") (pinfunction "1_1") (pintype "passive"))
    )
    (net (code "65") (name "A8") (class "Default")
      (node (ref "ARDUINO_DUE1") (pin "A8") (pinfunction "AN8_A8") (pintype "bidirectional"))
      (node (ref "JP15") (pin "8") (pinfunction "8_8") (pintype "passive"))
    )
    (net (code "66") (name "A9") (class "Default")
      (node (ref "ARDUINO_DUE1") (pin "A9") (pinfunction "AN9_A9") (pintype "bidirectional"))
      (node (ref "JP15") (pin "7") (pinfunction "7_7") (pintype "passive"))
    )
    (net (code "67") (name "A10") (class "Default")
      (node (ref "ARDUINO_DUE1") (pin "A10") (pinfunction "AN10_A10") (pintype "bidirectional"))
      (node (ref "JP15") (pin "6") (pinfunction "6_6") (pintype "passive"))
    )
    (net (code "68") (name "A11") (class "Default")
      (node (ref "ARDUINO_DUE1") (pin "A11") (pinfunction "AN11_A11") (pintype "bidirectional"))
      (node (ref "JP15") (pin "5") (pinfunction "5_5") (pintype "passive"))
    )
    (net (code "69") (name "CANRX") (class "Default")
      (node (ref "ARDUINO_DUE1") (pin "CANRX") (pinfunction "CANRX_CANRX") (pintype "bidirectional"))
      (node (ref "JP15") (pin "2") (pinfunction "2_2") (pintype "passive"))
    )
    (net (code "70") (name "CANTX") (class "Default")
      (node (ref "ARDUINO_DUE1") (pin "CANTX") (pinfunction "CANTX_CANTX") (pintype "bidirectional"))
      (node (ref "JP15") (pin "1") (pinfunction "1_1") (pintype "passive"))
    )
    (net (code "71") (name "D") (class "Default")
      (node (ref "F1") (pin "2") (pinfunction "2_2") (pintype "passive"))
      (node (ref "F2") (pin "1") (pinfunction "1_1") (pintype "passive"))
      (node (ref "F3") (pin "1") (pinfunction "1_1") (pintype "passive"))
      (node (ref "F4") (pin "1") (pinfunction "1_1") (pintype "passive"))
      (node (ref "F5") (pin "1") (pinfunction "1_1") (pintype "passive"))
    )
    (net (code "72") (name "DAC0") (class "Default")
      (node (ref "ARDUINO_DUE1") (pin "DAC0") (pinfunction "DAC0_DAC0") (pintype "bidirectional"))
      (node (ref "JP15") (pin "4") (pinfunction "4_4") (pintype "passive"))
    )
    (net (code "73") (name "DAC1") (class "Default")
      (node (ref "ARDUINO_DUE1") (pin "DAC1") (pinfunction "DAC1_DAC1") (pintype "bidirectional"))
      (node (ref "JP15") (pin "3") (pinfunction "3_3") (pintype "passive"))
    )
    (net (code "74") (name "EN1") (class "Default")
      (node (ref "JP2") (pin "3") (pinfunction "3_3") (pintype "passive"))
      (node (ref "R36") (pin "1") (pinfunction "1_1") (pintype "passive"))
      (node (ref "R37") (pin "1") (pinfunction "1_1") (pintype "passive"))
    )
    (net (code "75") (name "EN2") (class "Default")
      (node (ref "JP2") (pin "4") (pinfunction "4_4") (pintype "passive"))
      (node (ref "R33") (pin "1") (pinfunction "1_1") (pintype "passive"))
      (node (ref "R34") (pin "1") (pinfunction "1_1") (pintype "passive"))
    )
    (net (code "76") (name "EN3") (class "Default")
      (node (ref "JP1") (pin "3") (pinfunction "3_3") (pintype "passive"))
      (node (ref "R42") (pin "1") (pinfunction "1_1") (pintype "passive"))
      (node (ref "R43") (pin "1") (pinfunction "1_1") (pintype "passive"))
    )
    (net (code "77") (name "EN4") (class "Default")
      (node (ref "JP1") (pin "4") (pinfunction "4_4") (pintype "passive"))
      (node (ref "R39") (pin "1") (pinfunction "1_1") (pintype "passive"))
      (node (ref "R40") (pin "1") (pinfunction "1_1") (pintype "passive"))
    )
    (net (code "78") (name "EN9") (class "Default")
      (node (ref "JP7") (pin "3") (pinfunction "3_3") (pintype "passive"))
      (node (ref "R60") (pin "1") (pinfunction "1_1") (pintype "passive"))
      (node (ref "R61") (pin "1") (pinfunction "1_1") (pintype "passive"))
    )
    (net (code "79") (name "EN10") (class "Default")
      (node (ref "JP7") (pin "4") (pinfunction "4_4") (pintype "passive"))
      (node (ref "R57") (pin "1") (pinfunction "1_1") (pintype "passive"))
      (node (ref "R58") (pin "1") (pinfunction "1_1") (pintype "passive"))
    )
    (net (code "80") (name "EN11") (class "Default")
      (node (ref "JP5") (pin "3") (pinfunction "3_3") (pintype "passive"))
      (node (ref "R66") (pin "1") (pinfunction "1_1") (pintype "passive"))
      (node (ref "R67") (pin "1") (pinfunction "1_1") (pintype "passive"))
    )
    (net (code "81") (name "EN12") (class "Default")
      (node (ref "JP5") (pin "4") (pinfunction "4_4") (pintype "passive"))
      (node (ref "R63") (pin "1") (pinfunction "1_1") (pintype "passive"))
      (node (ref "R64") (pin "1") (pinfunction "1_1") (pintype "passive"))
    )
    (net (code "82") (name "ENABLE") (class "Default")
      (node (ref "BLUETOOTH.MODULE") (pin "6") (pinfunction "6_6") (pintype "passive"))
    )
    (net (code "83") (name "GNND") (class "Default")
      (node (ref "1-1") (pin "GND") (pinfunction "GND_GND") (pintype "input"))
      (node (ref "1-2") (pin "GND") (pinfunction "GND_GND") (pintype "input"))
      (node (ref "1-7805") (pin "GND") (pinfunction "GND_GND") (pintype "input"))
      (node (ref "1-7809") (pin "GND") (pinfunction "GND_GND") (pintype "input"))
      (node (ref "2-7805") (pin "GND") (pinfunction "GND_GND") (pintype "input"))
      (node (ref "2-7809") (pin "GND") (pinfunction "GND_GND") (pintype "input"))
      (node (ref "ARDUINO_DUE1") (pin "GND_1") (pinfunction "GND_GND_1") (pintype "bidirectional"))
      (node (ref "ARDUINO_DUE1") (pin "GND_3") (pinfunction "GND_GND_3") (pintype "bidirectional"))
      (node (ref "BLUETOOTH.MODULE") (pin "4") (pinfunction "4_4") (pintype "passive"))
      (node (ref "C1") (pin "-") (pinfunction "-_-") (pintype "passive"))
      (node (ref "C2") (pin "2") (pinfunction "2_2") (pintype "passive"))
      (node (ref "C3") (pin "-") (pinfunction "-_-") (pintype "passive"))
      (node (ref "C4") (pin "2") (pinfunction "2_2") (pintype "passive"))
      (node (ref "C5") (pin "2") (pinfunction "2_2") (pintype "passive"))
      (node (ref "C6") (pin "-") (pinfunction "-_-") (pintype "passive"))
      (node (ref "GND") (pin "1") (pinfunction "1_1") (pintype "passive"))
      (node (ref "GND") (pin "2") (pinfunction "2_2") (pintype "passive"))
      (node (ref "GND") (pin "3") (pinfunction "3_3") (pintype "passive"))
      (node (ref "GND") (pin "4") (pinfunction "4_4") (pintype "passive"))
      (node (ref "GND") (pin "5") (pinfunction "5_5") (pintype "passive"))
      (node (ref "GND1") (pin "1") (pinfunction "1_1") (pintype "passive"))
      (node (ref "GND1") (pin "2") (pinfunction "2_2") (pintype "passive"))
      (node (ref "GND1") (pin "3") (pinfunction "3_3") (pintype "passive"))
      (node (ref "GND1") (pin "4") (pinfunction "4_4") (pintype "passive"))
      (node (ref "GND1") (pin "5") (pinfunction "5_5") (pintype "passive"))
      (node (ref "IC1") (pin "8") (pinfunction "GND_8") (pintype "power_in"))
      (node (ref "IC2") (pin "8") (pinfunction "GND_8") (pintype "power_in"))
      (node (ref "IC3") (pin "8") (pinfunction "GND_8") (pintype "power_in"))
      (node (ref "JP1") (pin "2") (pinfunction "2_2") (pintype "passive"))
      (node (ref "JP11") (pin "5") (pinfunction "5_5") (pintype "passive"))
      (node (ref "JP13") (pin "5") (pinfunction "5_5") (pintype "passive"))
      (node (ref "JP2") (pin "2") (pinfunction "2_2") (pintype "passive"))
      (node (ref "JP4") (pin "5") (pinfunction "5_5") (pintype "passive"))
      (node (ref "JP5") (pin "2") (pinfunction "2_2") (pintype "passive"))
      (node (ref "JP7") (pin "2") (pinfunction "2_2") (pintype "passive"))
      (node (ref "JP8") (pin "5") (pinfunction "5_5") (pintype "passive"))
      (node (ref "MAIN_POWER") (pin "1") (pinfunction "KL_1") (pintype "passive"))
      (node (ref "R1") (pin "1") (pinfunction "1_1") (pintype "passive"))
      (node (ref "R2") (pin "1") (pinfunction "1_1") (pintype "passive"))
      (node (ref "R3") (pin "1") (pinfunction "1_1") (pintype "passive"))
      (node (ref "R35") (pin "1") (pinfunction "1_1") (pintype "passive"))
      (node (ref "R38") (pin "1") (pinfunction "1_1") (pintype "passive"))
      (node (ref "R4") (pin "1") (pinfunction "1_1") (pintype "passive"))
      (node (ref "R41") (pin "1") (pinfunction "1_1") (pintype "passive"))
      (node (ref "R44") (pin "1") (pinfunction "1_1") (pintype "passive"))
      (node (ref "R5") (pin "1") (pinfunction "1_1") (pintype "passive"))
      (node (ref "R59") (pin "1") (pinfunction "1_1") (pintype "passive"))
      (node (ref "R6") (pin "1") (pinfunction "1_1") (pintype "passive"))
      (node (ref "R62") (pin "1") (pinfunction "1_1") (pintype "passive"))
      (node (ref "R65") (pin "1") (pinfunction "1_1") (pintype "passive"))
      (node (ref "R68") (pin "1") (pinfunction "1_1") (pintype "passive"))
      (node (ref "U$1") (pin "J1.2") (pinfunction "GND.I_J1.2") (pintype "bidirectional"))
      (node (ref "X1") (pin "1") (pinfunction "KL_1") (pintype "passive"))
      (node (ref "X2") (pin "1") (pinfunction "KL_1") (pintype "passive"))
      (node (ref "X4") (pin "1") (pinfunction "KL_1") (pintype "passive"))
      (node (ref "X5") (pin "1") (pinfunction "KL_1") (pintype "passive"))
      (node (ref "X6") (pin "GND") (pinfunction "GND_GND") (pintype "bidirectional"))
      (node (ref "X7") (pin "GND") (pinfunction "GND_GND") (pintype "bidirectional"))
    )
    (net (code "84") (name "N$15") (class "Default")
      (node (ref "ARDUINO_DUE1") (pin "GND_2") (pinfunction "GND_GND_2") (pintype "bidirectional"))
    )
    (net (code "85") (name "N$50") (class "Default")
      (node (ref "ARDUINO_DUE1") (pin "5V0_2") (pinfunction "5V_5V0_2") (pintype "bidirectional"))
    )
    (net (code "86") (name "N$65") (class "Default")
      (node (ref "ARDUINO_DUE1") (pin "14") (pinfunction "TX3_14_14") (pintype "bidirectional"))
    )
    (net (code "87") (name "N$66") (class "Default")
      (node (ref "ARDUINO_DUE1") (pin "15") (pinfunction "RX3_15_15") (pintype "bidirectional"))
    )
    (net (code "88") (name "N$67") (class "Default")
      (node (ref "ARDUINO_DUE1") (pin "16") (pinfunction "TX2_16_16") (pintype "bidirectional"))
    )
    (net (code "89") (name "N$68") (class "Default")
      (node (ref "ARDUINO_DUE1") (pin "17") (pinfunction "RX2_17_17") (pintype "bidirectional"))
    )
    (net (code "90") (name "N$69") (class "Default")
      (node (ref "ARDUINO_DUE1") (pin "18") (pinfunction "TX1_18_18") (pintype "bidirectional"))
    )
    (net (code "91") (name "N$70") (class "Default")
      (node (ref "ARDUINO_DUE1") (pin "19") (pinfunction "RX1_19_19") (pintype "bidirectional"))
    )
    (net (code "92") (name "N$71") (class "Default")
      (node (ref "ARDUINO_DUE1") (pin "20") (pinfunction "SDA_20_20") (pintype "bidirectional"))
    )
    (net (code "93") (name "N$72") (class "Default")
      (node (ref "ARDUINO_DUE1") (pin "21") (pinfunction "SCL_21_21") (pintype "bidirectional"))
    )
    (net (code "94") (name "N$73") (class "Default")
      (node (ref "ARDUINO_DUE1") (pin "SCL1") (pinfunction "SCL1_SCL1") (pintype "bidirectional"))
    )
    (net (code "95") (name "N$74") (class "Default")
      (node (ref "ARDUINO_DUE1") (pin "SDA1") (pinfunction "SDA1_SDA1") (pintype "bidirectional"))
    )
    (net (code "96") (name "N$75") (class "Default")
      (node (ref "ARDUINO_DUE1") (pin "AREF") (pinfunction "AREF_AREF") (pintype "bidirectional"))
    )
    (net (code "97") (name "N$76") (class "Default")
      (node (ref "ARDUINO_DUE1") (pin "GND_4") (pinfunction "GND_GND_4") (pintype "bidirectional"))
    )
    (net (code "99") (name "N$78") (class "Default")
      (node (ref "ARDUINO_DUE1") (pin "IOREF") (pinfunction "IOREF_IOREF") (pintype "bidirectional"))
    )
    (net (code "100") (name "N$79") (class "Default")
      (node (ref "ARDUINO_DUE1") (pin "RESET") (pinfunction "RESET_RESET") (pintype "bidirectional"))
    )
    (net (code "101") (name "N$82") (class "Default")
      (node (ref "ARDUINO_DUE1") (pin "GND") (pinfunction "GND_GND") (pintype "bidirectional"))
    )
    (net (code "102") (name "Net-(1-7805-PadIN)") (class "Default")
      (node (ref "1-7805") (pin "IN") (pinfunction "IN_IN") (pintype "input"))
      (node (ref "1-7809") (pin "OUT") (pinfunction "OUT_OUT") (pintype "passive"))
      (node (ref "C3") (pin "+") (pinfunction "+_+") (pintype "passive"))
      (node (ref "LED3") (pin "A") (pinfunction "A_A") (pintype "passive"))
    )
    (net (code "103") (name "Net-(2-7805-PadIN)") (class "Default")
      (node (ref "2-7805") (pin "IN") (pinfunction "IN_IN") (pintype "input"))
      (node (ref "2-7809") (pin "OUT") (pinfunction "OUT_OUT") (pintype "passive"))
      (node (ref "C6") (pin "+") (pinfunction "+_+") (pintype "passive"))
      (node (ref "LED5") (pin "A") (pinfunction "A_A") (pintype "passive"))
    )
    (net (code "104") (name "Net-(C2-Pad1)") (class "Default")
      (node (ref "C2") (pin "1") (pinfunction "1_1") (pintype "passive"))
      (node (ref "LED2") (pin "A") (pinfunction "A_A") (pintype "passive"))
    )
    (net (code "105") (name "Net-(LED1-C)") (class "Default")
      (node (ref "LED1") (pin "K") (pinfunction "C_K") (pintype "passive"))
      (node (ref "R1") (pin "2") (pinfunction "2_2") (pintype "passive"))
    )
    (net (code "106") (name "Net-(LED2-C)") (class "Default")
      (node (ref "LED2") (pin "K") (pinfunction "C_K") (pintype "passive"))
      (node (ref "R2") (pin "2") (pinfunction "2_2") (pintype "passive"))
    )
    (net (code "107") (name "Net-(LED3-C)") (class "Default")
      (node (ref "LED3") (pin "K") (pinfunction "C_K") (pintype "passive"))
      (node (ref "R4") (pin "2") (pinfunction "2_2") (pintype "passive"))
    )
    (net (code "108") (name "Net-(LED4-C)") (class "Default")
      (node (ref "LED4") (pin "K") (pinfunction "C_K") (pintype "passive"))
      (node (ref "R3") (pin "2") (pinfunction "2_2") (pintype "passive"))
    )
    (net (code "109") (name "Net-(LED5-C)") (class "Default")
      (node (ref "LED5") (pin "K") (pinfunction "C_K") (pintype "passive"))
      (node (ref "R5") (pin "2") (pinfunction "2_2") (pintype "passive"))
    )
    (net (code "110") (name "Net-(LED6-C)") (class "Default")
      (node (ref "LED6") (pin "K") (pinfunction "C_K") (pintype "passive"))
      (node (ref "R6") (pin "2") (pinfunction "2_2") (pintype "passive"))
    )
    (net (code "111") (name "Net-(LED7-C)") (class "Default")
      (node (ref "LED7") (pin "K") (pinfunction "C_K") (pintype "passive"))
      (node (ref "R7") (pin "2") (pinfunction "2_2") (pintype "passive"))
    )
    (net (code "112") (name "Net-(LED8-C)") (class "Default")
      (node (ref "LED8") (pin "K") (pinfunction "C_K") (pintype "passive"))
      (node (ref "R8") (pin "2") (pinfunction "2_2") (pintype "passive"))
    )
    (net (code "113") (name "Net-(LED9-C)") (class "Default")
      (node (ref "LED9") (pin "K") (pinfunction "C_K") (pintype "passive"))
      (node (ref "R9") (pin "2") (pinfunction "2_2") (pintype "passive"))
    )
    (net (code "114") (name "Net-(LED10-C)") (class "Default")
      (node (ref "LED10") (pin "K") (pinfunction "C_K") (pintype "passive"))
      (node (ref "R10") (pin "2") (pinfunction "2_2") (pintype "passive"))
    )
    (net (code "115") (name "Net-(LED11-C)") (class "Default")
      (node (ref "LED11") (pin "K") (pinfunction "C_K") (pintype "passive"))
      (node (ref "R11") (pin "2") (pinfunction "2_2") (pintype "passive"))
    )
    (net (code "116") (name "Net-(LED12-C)") (class "Default")
      (node (ref "LED12") (pin "K") (pinfunction "C_K") (pintype "passive"))
      (node (ref "R12") (pin "2") (pinfunction "2_2") (pintype "passive"))
    )
    (net (code "117") (name "Net-(LED13-C)") (class "Default")
      (node (ref "LED13") (pin "K") (pinfunction "C_K") (pintype "passive"))
      (node (ref "R13") (pin "2") (pinfunction "2_2") (pintype "passive"))
    )
    (net (code "118") (name "Net-(LED14-C)") (class "Default")
      (node (ref "LED14") (pin "K") (pinfunction "C_K") (pintype "passive"))
      (node (ref "R14") (pin "2") (pinfunction "2_2") (pintype "passive"))
    )
    (net (code "119") (name "Net-(Q1-PadB)") (class "Default")
      (node (ref "Q1") (pin "B") (pinfunction "B_B") (pintype "passive"))
      (node (ref "R36") (pin "2") (pinfunction "2_2") (pintype "passive"))
    )
    (net (code "120") (name "Net-(Q2-PadB)") (class "Default")
      (node (ref "Q2") (pin "B") (pinfunction "B_B") (pintype "passive"))
      (node (ref "R33") (pin "2") (pinfunction "2_2") (pintype "passive"))
    )
    (net (code "121") (name "Net-(Q3-PadB)") (class "Default")
      (node (ref "Q3") (pin "B") (pinfunction "B_B") (pintype "passive"))
      (node (ref "R42") (pin "2") (pinfunction "2_2") (pintype "passive"))
    )
    (net (code "122") (name "Net-(Q4-PadB)") (class "Default")
      (node (ref "Q4") (pin "B") (pinfunction "B_B") (pintype "passive"))
      (node (ref "R39") (pin "2") (pinfunction "2_2") (pintype "passive"))
    )
    (net (code "123") (name "Net-(Q9-PadB)") (class "Default")
      (node (ref "Q9") (pin "B") (pinfunction "B_B") (pintype "passive"))
      (node (ref "R60") (pin "2") (pinfunction "2_2") (pintype "passive"))
    )
    (net (code "124") (name "Net-(Q10-PadB)") (class "Default")
      (node (ref "Q10") (pin "B") (pinfunction "B_B") (pintype "passive"))
      (node (ref "R57") (pin "2") (pinfunction "2_2") (pintype "passive"))
    )
    (net (code "125") (name "Net-(Q11-PadB)") (class "Default")
      (node (ref "Q11") (pin "B") (pinfunction "B_B") (pintype "passive"))
      (node (ref "R66") (pin "2") (pinfunction "2_2") (pintype "passive"))
    )
    (net (code "126") (name "Net-(Q12-PadB)") (class "Default")
      (node (ref "Q12") (pin "B") (pinfunction "B_B") (pintype "passive"))
      (node (ref "R63") (pin "2") (pinfunction "2_2") (pintype "passive"))
    )
    (net (code "127") (name "O1") (class "Default")
      (node (ref "IC1") (pin "16") (pinfunction "O1_16") (pintype "open_collector"))
      (node (ref "LED7") (pin "A") (pinfunction "A_A") (pintype "passive"))
      (node (ref "X3") (pin "1") (pinfunction "KL_1") (pintype "passive"))
    )
    (net (code "128") (name "O2") (class "Default")
      (node (ref "IC1") (pin "15") (pinfunction "O2_15") (pintype "open_collector"))
      (node (ref "LED9") (pin "A") (pinfunction "A_A") (pintype "passive"))
      (node (ref "X10") (pin "1") (pinfunction "KL_1") (pintype "passive"))
    )
    (net (code "129") (name "O3") (class "Default")
      (node (ref "IC1") (pin "14") (pinfunction "O3_14") (pintype "open_collector"))
      (node (ref "LED8") (pin "A") (pinfunction "A_A") (pintype "passive"))
      (node (ref "X8") (pin "1") (pinfunction "KL_1") (pintype "passive"))
    )
    (net (code "130") (name "O4") (class "Default")
      (node (ref "IC1") (pin "13") (pinfunction "O4_13") (pintype "open_collector"))
      (node (ref "LED10") (pin "A") (pinfunction "A_A") (pintype "passive"))
      (node (ref "X9") (pin "1") (pinfunction "KL_1") (pintype "passive"))
    )
    (net (code "131") (name "O5") (class "Default")
      (node (ref "IC2") (pin "16") (pinfunction "O1_16") (pintype "open_collector"))
      (node (ref "LED12") (pin "A") (pinfunction "A_A") (pintype "passive"))
      (node (ref "X11") (pin "1") (pinfunction "KL_1") (pintype "passive"))
    )
    (net (code "132") (name "O6") (class "Default")
      (node (ref "IC2") (pin "15") (pinfunction "O2_15") (pintype "open_collector"))
      (node (ref "LED13") (pin "A") (pinfunction "A_A") (pintype "passive"))
      (node (ref "X14") (pin "1") (pinfunction "KL_1") (pintype "passive"))
    )
    (net (code "133") (name "O7") (class "Default")
      (node (ref "IC2") (pin "14") (pinfunction "O3_14") (pintype "open_collector"))
      (node (ref "LED11") (pin "A") (pinfunction "A_A") (pintype "passive"))
      (node (ref "X12") (pin "1") (pinfunction "KL_1") (pintype "passive"))
    )
    (net (code "134") (name "O8") (class "Default")
      (node (ref "IC2") (pin "13") (pinfunction "O4_13") (pintype "open_collector"))
      (node (ref "LED14") (pin "A") (pinfunction "A_A") (pintype "passive"))
      (node (ref "X13") (pin "1") (pinfunction "KL_1") (pintype "passive"))
    )
    (net (code "135") (name "O9") (class "Default")
      (node (ref "IC3") (pin "16") (pinfunction "O1_16") (pintype "open_collector"))
      (node (ref "X15") (pin "1") (pinfunction "KL_1") (pintype "passive"))
    )
    (net (code "136") (name "O10") (class "Default")
      (node (ref "IC3") (pin "15") (pinfunction "O2_15") (pintype "open_collector"))
      (node (ref "X16") (pin "1") (pinfunction "KL_1") (pintype "passive"))
    )
    (net (code "137") (name "O11") (class "Default")
      (node (ref "IC3") (pin "14") (pinfunction "O3_14") (pintype "open_collector"))
      (node (ref "X17") (pin "1") (pinfunction "KL_1") (pintype "passive"))
    )
    (net (code "138") (name "O12") (class "Default")
      (node (ref "IC3") (pin "13") (pinfunction "O4_13") (pintype "open_collector"))
      (node (ref "X18") (pin "1") (pinfunction "KL_1") (pintype "passive"))
    )
    (net (code "139") (name "RX0") (class "Default")
      (node (ref "ARDUINO_DUE1") (pin "0") (pinfunction "RX0<0_0") (pintype "bidirectional"))
      (node (ref "BLUETOOTH.MODULE") (pin "3") (pinfunction "3_3") (pintype "passive"))
    )
    (net (code "140") (name "STATE") (class "Default")
      (node (ref "BLUETOOTH.MODULE") (pin "1") (pinfunction "1_1") (pintype "passive"))
    )
    (net (code "141") (name "TX0") (class "Default")
      (node (ref "ARDUINO_DUE1") (pin "1") (pinfunction "TX0>1_1") (pintype "bidirectional"))
      (node (ref "BLUETOOTH.MODULE") (pin "2") (pinfunction "2_2") (pintype "passive"))
    )
    (net (code "142") (name "VCC") (class "Default")
      (node (ref "2-7805") (pin "OUT") (pinfunction "OUT_OUT") (pintype "passive"))
      (node (ref "C4") (pin "1") (pinfunction "1_1") (pintype "passive"))
      (node (ref "JP5") (pin "1") (pinfunction "1_1") (pintype "passive"))
      (node (ref "JP7") (pin "1") (pinfunction "1_1") (pintype "passive"))
      (node (ref "LED6") (pin "A") (pinfunction "A_A") (pintype "passive"))
      (node (ref "R58") (pin "2") (pinfunction "2_2") (pintype "passive"))
      (node (ref "R61") (pin "2") (pinfunction "2_2") (pintype "passive"))
      (node (ref "R64") (pin "2") (pinfunction "2_2") (pintype "passive"))
      (node (ref "R67") (pin "2") (pinfunction "2_2") (pintype "passive"))
    )
    (net (code "143") (name "VCC1") (class "Default")
      (node (ref "1-7805") (pin "OUT") (pinfunction "OUT_OUT") (pintype "passive"))
      (node (ref "C5") (pin "1") (pinfunction "1_1") (pintype "passive"))
      (node (ref "JP1") (pin "1") (pinfunction "1_1") (pintype "passive"))
      (node (ref "JP2") (pin "1") (pinfunction "1_1") (pintype "passive"))
      (node (ref "LED4") (pin "A") (pinfunction "A_A") (pintype "passive"))
      (node (ref "R34") (pin "2") (pinfunction "2_2") (pintype "passive"))
      (node (ref "R37") (pin "2") (pinfunction "2_2") (pintype "passive"))
      (node (ref "R40") (pin "2") (pinfunction "2_2") (pintype "passive"))
      (node (ref "R43") (pin "2") (pinfunction "2_2") (pintype "passive"))
      (node (ref "U$1") (pin "J1.1") (pinfunction "VIN_J1.1") (pintype "bidirectional"))
      (node (ref "VCC_REG") (pin "1") (pinfunction "1_1") (pintype "passive"))
      (node (ref "VCC_REG") (pin "2") (pinfunction "2_2") (pintype "passive"))
      (node (ref "VCC_REG") (pin "3") (pinfunction "3_3") (pintype "passive"))
      (node (ref "VCC_REG") (pin "4") (pinfunction "4_4") (pintype "passive"))
      (node (ref "VCC_REG") (pin "5") (pinfunction "5_5") (pintype "passive"))
    )
    (net (code "144") (name "VCC2") (class "Default")
      (node (ref "1-2") (pin "OUT") (pinfunction "OUT_OUT") (pintype "passive"))
      (node (ref "X6") (pin "VBUS") (pinfunction "VBUS_VBUS") (pintype "bidirectional"))
      (node (ref "X7") (pin "VBUS") (pinfunction "VBUS_VBUS") (pintype "bidirectional"))
    )
    (net (code "145") (name "unconnected-(ARDUINO_DUE1-NC-PadNC_2)") (class "Default")
      (node (ref "ARDUINO_DUE1") (pin "NC_2") (pinfunction "NC_NC_2") (pintype "no_connect"))
    )
    (net (code "146") (name "unconnected-(IC1-I5-Pad5)") (class "Default")
      (node (ref "IC1") (pin "5") (pinfunction "I5_5") (pintype "input"))
    )
    (net (code "147") (name "unconnected-(IC1-I6-Pad6)") (class "Default")
      (node (ref "IC1") (pin "6") (pinfunction "I6_6") (pintype "input"))
    )
    (net (code "148") (name "unconnected-(IC1-I7-Pad7)") (class "Default")
      (node (ref "IC1") (pin "7") (pinfunction "I7_7") (pintype "input"))
    )
    (net (code "149") (name "unconnected-(IC1-O5-Pad12)") (class "Default")
      (node (ref "IC1") (pin "12") (pinfunction "O5_12") (pintype "open_collector"))
    )
    (net (code "150") (name "unconnected-(IC1-O6-Pad11)") (class "Default")
      (node (ref "IC1") (pin "11") (pinfunction "O6_11") (pintype "open_collector"))
    )
    (net (code "151") (name "unconnected-(IC1-O7-Pad10)") (class "Default")
      (node (ref "IC1") (pin "10") (pinfunction "O7_10") (pintype "open_collector"))
    )
    (net (code "152") (name "unconnected-(IC2-I5-Pad5)") (class "Default")
      (node (ref "IC2") (pin "5") (pinfunction "I5_5") (pintype "input"))
    )
    (net (code "153") (name "unconnected-(IC2-I6-Pad6)") (class "Default")
      (node (ref "IC2") (pin "6") (pinfunction "I6_6") (pintype "input"))
    )
    (net (code "154") (name "unconnected-(IC2-I7-Pad7)") (class "Default")
      (node (ref "IC2") (pin "7") (pinfunction "I7_7") (pintype "input"))
    )
    (net (code "155") (name "unconnected-(IC2-O5-Pad12)") (class "Default")
      (node (ref "IC2") (pin "12") (pinfunction "O5_12") (pintype "open_collector"))
    )
    (net (code "156") (name "unconnected-(IC2-O6-Pad11)") (class "Default")
      (node (ref "IC2") (pin "11") (pinfunction "O6_11") (pintype "open_collector"))
    )
    (net (code "157") (name "unconnected-(IC2-O7-Pad10)") (class "Default")
      (node (ref "IC2") (pin "10") (pinfunction "O7_10") (pintype "open_collector"))
    )
    (net (code "158") (name "unconnected-(IC3-I5-Pad5)") (class "Default")
      (node (ref "IC3") (pin "5") (pinfunction "I5_5") (pintype "input"))
    )
    (net (code "159") (name "unconnected-(IC3-I6-Pad6)") (class "Default")
      (node (ref "IC3") (pin "6") (pinfunction "I6_6") (pintype "input"))
    )
    (net (code "160") (name "unconnected-(IC3-I7-Pad7)") (class "Default")
      (node (ref "IC3") (pin "7") (pinfunction "I7_7") (pintype "input"))
    )
    (net (code "161") (name "unconnected-(IC3-O5-Pad12)") (class "Default")
      (node (ref "IC3") (pin "12") (pinfunction "O5_12") (pintype "open_collector"))
    )
    (net (code "162") (name "unconnected-(IC3-O6-Pad11)") (class "Default")
      (node (ref "IC3") (pin "11") (pinfunction "O6_11") (pintype "open_collector"))
    )
    (net (code "163") (name "unconnected-(IC3-O7-Pad10)") (class "Default")
      (node (ref "IC3") (pin "10") (pinfunction "O7_10") (pintype "open_collector"))
    )
    (net (code "164") (name "unconnected-(U$1-GND.O-PadJ2.2)") (class "Default")
      (node (ref "U$1") (pin "J2.2") (pinfunction "GND.O_J2.2") (pintype "bidirectional"))
    )
    (net (code "165") (name "unconnected-(X6-PadD+)") (class "Default")
      (node (ref "X6") (pin "D+") (pinfunction "D+_D+") (pintype "bidirectional"))
    )
    (net (code "166") (name "unconnected-(X6-PadD-)") (class "Default")
      (node (ref "X6") (pin "D-") (pinfunction "D-_D-") (pintype "bidirectional"))
    )
    (net (code "167") (name "unconnected-(X7-PadD+)") (class "Default")
      (node (ref "X7") (pin "D+") (pinfunction "D+_D+") (pintype "bidirectional"))
    )
    (net (code "168") (name "unconnected-(X7-PadD-)") (class "Default")
      (node (ref "X7") (pin "D-") (pinfunction "D-_D-") (pintype "bidirectional"))
    )
  )
)
